# CAM-M8Q-Breakout_v10.net
KiCad netlist of a schematic drawn in EAGLE
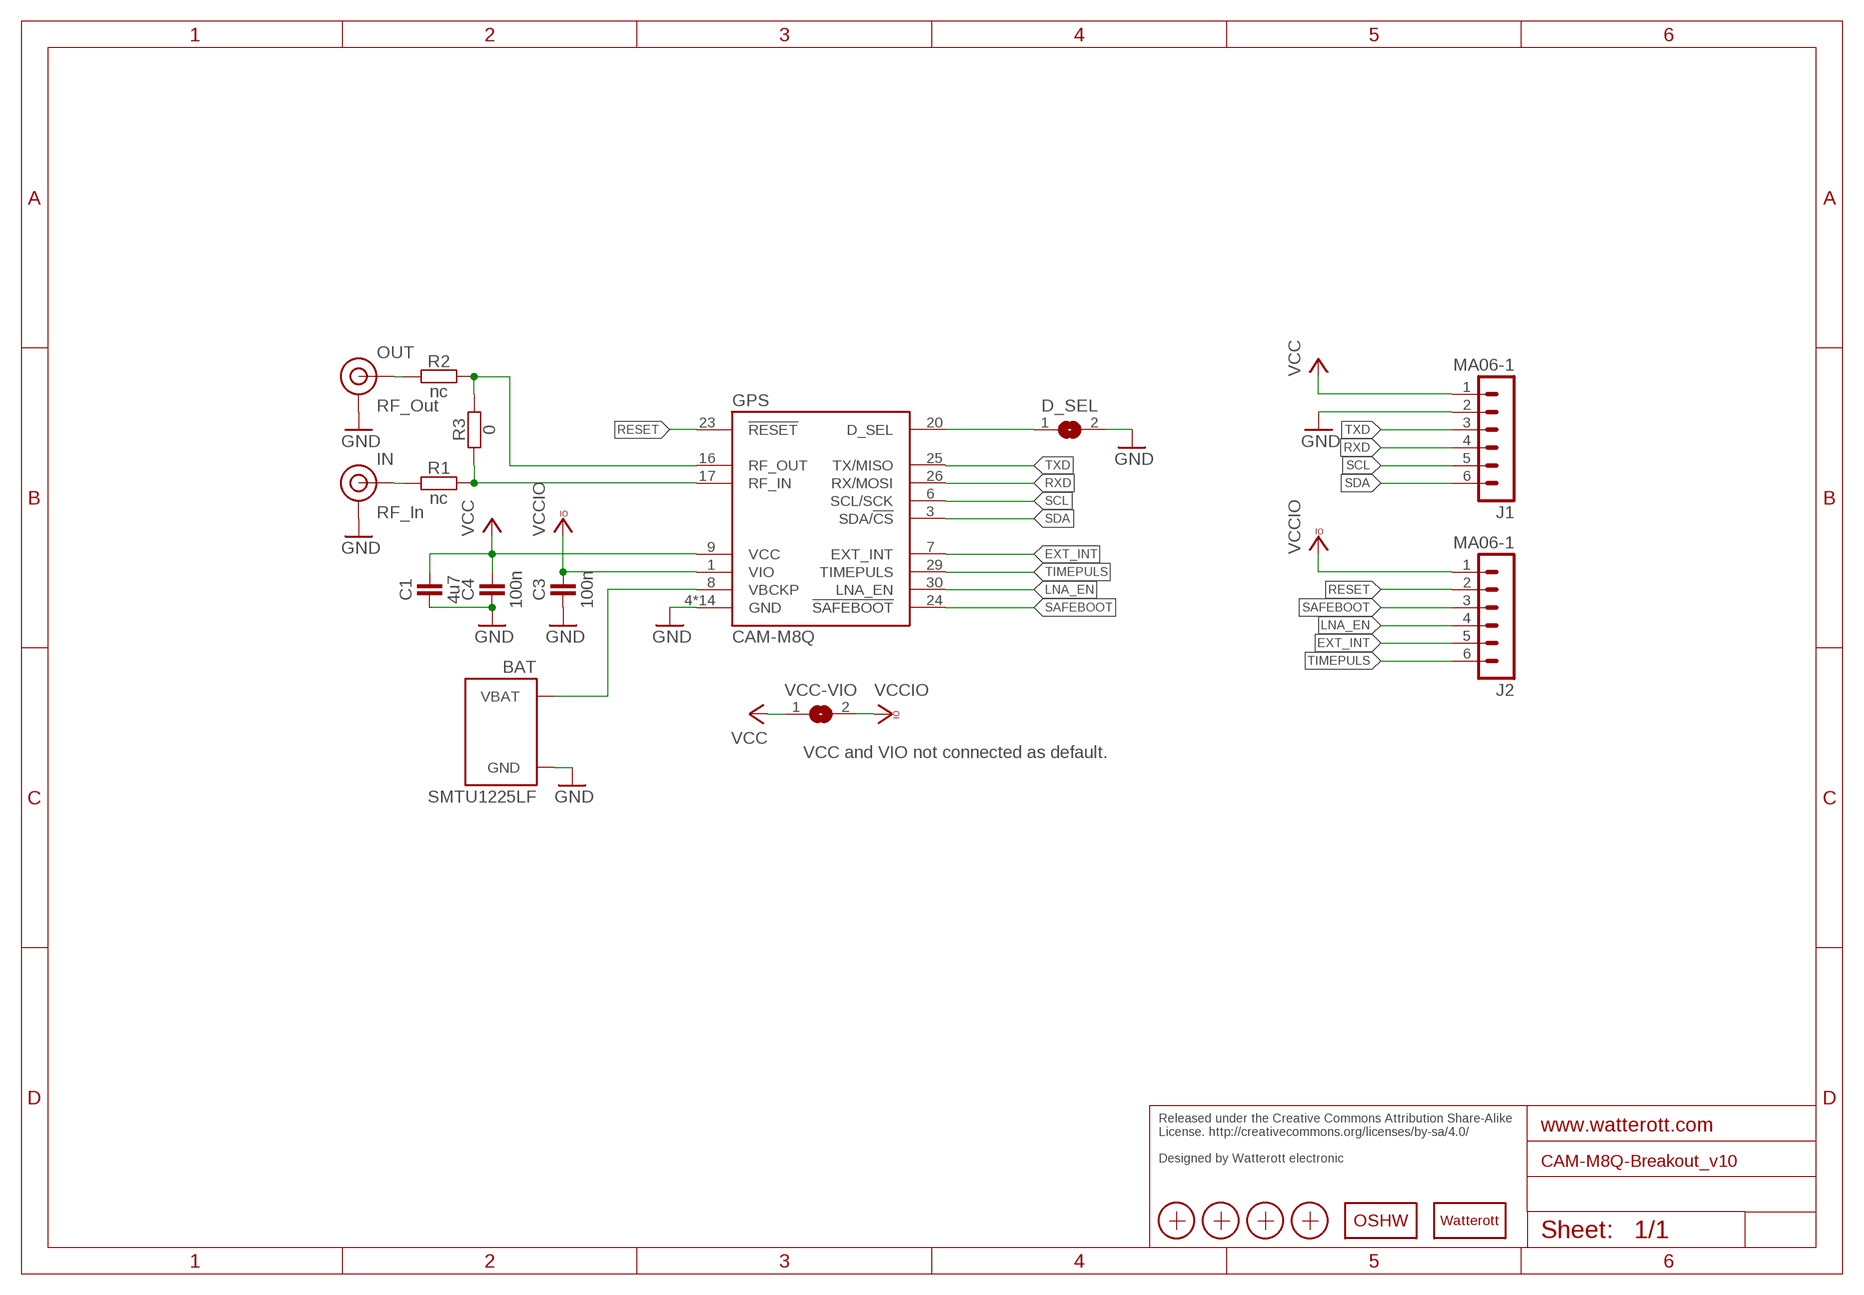
[diagram p0: schematic, sheet 1]

(export (version "E")
  (design (tool "Eeschema 10.0.6"))
  (components
    (comp (ref "BAT")
      (value "SMTU1225LF")
      (footprint "eagle-import:BAT-SMTU1225LF")
      (libsource (lib "eagle-import") (part "BATTERY-SMTU1225LF"))
    )
    (comp (ref "C1")
      (value "4u7")
      (footprint "eagle-import:C0402")
      (libsource (lib "eagle-import") (part "CAPACITOR-0402"))
    )
    (comp (ref "C3")
      (value "100n")
      (footprint "eagle-import:C0402")
      (libsource (lib "eagle-import") (part "CAPACITOR-0402"))
    )
    (comp (ref "C4")
      (value "100n")
      (footprint "eagle-import:C0402")
      (libsource (lib "eagle-import") (part "CAPACITOR-0402"))
    )
    (comp (ref "D_SEL")
      (value "JUMPER2-0603-NC")
      (footprint "eagle-import:JUMPER2-0603_NC")
      (libsource (lib "eagle-import") (part "JUMPER2-0603-NC"))
    )
    (comp (ref "GPS")
      (value "CAM-M8Q")
      (footprint "eagle-import:CAM-M8Q")
      (libsource (lib "eagle-import") (part "CAM-M8Q"))
    )
    (comp (ref "IN")
      (value "RF_In")
      (footprint "eagle-import:U.FL")
      (libsource (lib "eagle-import") (part "U.FL"))
    )
    (comp (ref "J1")
      (value "MA06-1")
      (footprint "eagle-import:MA06-1")
      (libsource (lib "eagle-import") (part "MA06-1"))
    )
    (comp (ref "J2")
      (value "MA06-1")
      (footprint "eagle-import:MA06-1")
      (libsource (lib "eagle-import") (part "MA06-1"))
    )
    (comp (ref "LOGO1")
      (value "LOGO-S_PLACE_M")
      (footprint "eagle-import:SPARK_TPLACE_M")
      (libsource (lib "eagle-import") (part "LOGO-S_PLACE_M"))
    )
    (comp (ref "LOGO2")
      (value "OSHW_LOGOX0070")
      (footprint "eagle-import:OSHW_6X70")
      (libsource (lib "eagle-import") (part "OSHW_LOGOX0070"))
    )
    (comp (ref "OUT")
      (value "RF_Out")
      (footprint "eagle-import:U.FL")
      (libsource (lib "eagle-import") (part "U.FL"))
    )
    (comp (ref "R1")
      (value "nc")
      (footprint "eagle-import:C0402")
      (libsource (lib "eagle-import") (part "RESISTOR-0402"))
    )
    (comp (ref "R2")
      (value "nc")
      (footprint "eagle-import:C0402")
      (libsource (lib "eagle-import") (part "RESISTOR-0402"))
    )
    (comp (ref "R3")
      (value "0")
      (footprint "eagle-import:C0402")
      (libsource (lib "eagle-import") (part "RESISTOR-0402"))
    )
    (comp (ref "VCC-VIO")
      (value "JUMPER2-0603-NC")
      (footprint "eagle-import:JUMPER2-0603_NC")
      (libsource (lib "eagle-import") (part "JUMPER2-0603-NC"))
    )
    (comp (ref "X1")
      (value "PASSER-07")
      (footprint "eagle-import:PASSER_07MM")
      (libsource (lib "eagle-import") (part "PASSER-07"))
    )
    (comp (ref "X2")
      (value "PASSER-07")
      (footprint "eagle-import:PASSER_07MM")
      (libsource (lib "eagle-import") (part "PASSER-07"))
    )
    (comp (ref "X3")
      (value "PASSER-07")
      (footprint "eagle-import:PASSER_07MM")
      (libsource (lib "eagle-import") (part "PASSER-07"))
    )
    (comp (ref "X4")
      (value "PASSER-07")
      (footprint "eagle-import:PASSER_07MM")
      (libsource (lib "eagle-import") (part "PASSER-07"))
    )
  )
  (nets
    (net (code "1") (name "EXT_INT") (class "Default")
      (node (ref "GPS") (pin "7") (pinfunction "EXT_INT_7") (pintype "bidirectional"))
      (node (ref "J2") (pin "5") (pinfunction "5_5") (pintype "passive"))
    )
    (net (code "2") (name "GND") (class "Default")
      (node (ref "BAT") (pin "-") (pinfunction "GND_-") (pintype "power_in"))
      (node (ref "C1") (pin "1") (pinfunction "1_1") (pintype "passive"))
      (node (ref "C3") (pin "1") (pinfunction "1_1") (pintype "passive"))
      (node (ref "C4") (pin "1") (pinfunction "1_1") (pintype "passive"))
      (node (ref "D_SEL") (pin "2") (pinfunction "2_2") (pintype "passive"))
      (node (ref "GPS") (pin "10") (pinfunction "GND_10") (pintype "power_in"))
      (node (ref "GPS") (pin "11") (pinfunction "GND_11") (pintype "power_in"))
      (node (ref "GPS") (pin "12") (pinfunction "GND_12") (pintype "power_in"))
      (node (ref "GPS") (pin "13") (pinfunction "GND_13") (pintype "power_in"))
      (node (ref "GPS") (pin "14") (pinfunction "GND_14") (pintype "power_in"))
      (node (ref "GPS") (pin "15") (pinfunction "GND_15") (pintype "power_in"))
      (node (ref "GPS") (pin "18") (pinfunction "GND_18") (pintype "power_in"))
      (node (ref "GPS") (pin "19") (pinfunction "GND_19") (pintype "power_in"))
      (node (ref "GPS") (pin "21") (pinfunction "GND_21") (pintype "power_in"))
      (node (ref "GPS") (pin "22") (pinfunction "GND_22") (pintype "power_in"))
      (node (ref "GPS") (pin "27") (pinfunction "GND_27") (pintype "power_in"))
      (node (ref "GPS") (pin "31") (pinfunction "GND_31") (pintype "power_in"))
      (node (ref "GPS") (pin "4") (pinfunction "GND_4") (pintype "power_in"))
      (node (ref "GPS") (pin "5") (pinfunction "GND_5") (pintype "power_in"))
      (node (ref "IN") (pin "1") (pinfunction "GND_1") (pintype "bidirectional"))
      (node (ref "IN") (pin "2") (pinfunction "GND_2") (pintype "bidirectional"))
      (node (ref "J1") (pin "2") (pinfunction "2_2") (pintype "passive"))
      (node (ref "OUT") (pin "1") (pinfunction "GND_1") (pintype "bidirectional"))
      (node (ref "OUT") (pin "2") (pinfunction "GND_2") (pintype "bidirectional"))
    )
    (net (code "3") (name "LNA_EN") (class "Default")
      (node (ref "GPS") (pin "30") (pinfunction "LNA_EN_30") (pintype "bidirectional"))
      (node (ref "J2") (pin "4") (pinfunction "4_4") (pintype "passive"))
    )
    (net (code "4") (name "Net-(BAT-VBAT)") (class "Default")
      (node (ref "BAT") (pin "+") (pinfunction "VBAT_+") (pintype "power_in"))
      (node (ref "GPS") (pin "8") (pinfunction "VBCKP_8") (pintype "power_in"))
    )
    (net (code "5") (name "Net-(GPS-D_SEL)") (class "Default")
      (node (ref "D_SEL") (pin "1") (pinfunction "1_1") (pintype "passive"))
      (node (ref "GPS") (pin "20") (pinfunction "D_SEL_20") (pintype "bidirectional"))
    )
    (net (code "6") (name "Net-(GPS-RF_IN)") (class "Default")
      (node (ref "GPS") (pin "17") (pinfunction "RF_IN_17") (pintype "input"))
      (node (ref "R1") (pin "2") (pinfunction "2_2") (pintype "passive"))
      (node (ref "R3") (pin "1") (pinfunction "1_1") (pintype "passive"))
    )
    (net (code "7") (name "Net-(GPS-RF_OUT)") (class "Default")
      (node (ref "GPS") (pin "16") (pinfunction "RF_OUT_16") (pintype "output"))
      (node (ref "R2") (pin "2") (pinfunction "2_2") (pintype "passive"))
      (node (ref "R3") (pin "2") (pinfunction "2_2") (pintype "passive"))
    )
    (net (code "8") (name "Net-(IN-SIGNAL)") (class "Default")
      (node (ref "IN") (pin "FEED") (pinfunction "SIGNAL_FEED") (pintype "bidirectional"))
      (node (ref "R1") (pin "1") (pinfunction "1_1") (pintype "passive"))
    )
    (net (code "9") (name "Net-(OUT-SIGNAL)") (class "Default")
      (node (ref "OUT") (pin "FEED") (pinfunction "SIGNAL_FEED") (pintype "bidirectional"))
      (node (ref "R2") (pin "1") (pinfunction "1_1") (pintype "passive"))
    )
    (net (code "10") (name "RESET") (class "Default")
      (node (ref "GPS") (pin "23") (pinfunction "~{RESET}_23") (pintype "input"))
      (node (ref "J2") (pin "2") (pinfunction "2_2") (pintype "passive"))
    )
    (net (code "11") (name "RXD") (class "Default")
      (node (ref "GPS") (pin "26") (pinfunction "RX/MOSI_26") (pintype "input"))
      (node (ref "J1") (pin "4") (pinfunction "4_4") (pintype "passive"))
    )
    (net (code "12") (name "SAFEBOOT") (class "Default")
      (node (ref "GPS") (pin "24") (pinfunction "~{SAFEBOOT}_24") (pintype "bidirectional"))
      (node (ref "J2") (pin "3") (pinfunction "3_3") (pintype "passive"))
    )
    (net (code "13") (name "SCL") (class "Default")
      (node (ref "GPS") (pin "6") (pinfunction "SCL/SCK_6") (pintype "bidirectional"))
      (node (ref "J1") (pin "5") (pinfunction "5_5") (pintype "passive"))
    )
    (net (code "14") (name "SDA") (class "Default")
      (node (ref "GPS") (pin "3") (pinfunction "SDA/~{CS}_3") (pintype "bidirectional"))
      (node (ref "J1") (pin "6") (pinfunction "6_6") (pintype "passive"))
    )
    (net (code "15") (name "TIMEPULS") (class "Default")
      (node (ref "GPS") (pin "29") (pinfunction "TIMEPULS_29") (pintype "output"))
      (node (ref "J2") (pin "6") (pinfunction "6_6") (pintype "passive"))
    )
    (net (code "16") (name "TXD") (class "Default")
      (node (ref "GPS") (pin "25") (pinfunction "TX/MISO_25") (pintype "output"))
      (node (ref "J1") (pin "3") (pinfunction "3_3") (pintype "passive"))
    )
    (net (code "17") (name "VCC") (class "Default")
      (node (ref "C1") (pin "2") (pinfunction "2_2") (pintype "passive"))
      (node (ref "C4") (pin "2") (pinfunction "2_2") (pintype "passive"))
      (node (ref "GPS") (pin "9") (pinfunction "VCC_9") (pintype "power_in"))
      (node (ref "J1") (pin "1") (pinfunction "1_1") (pintype "passive"))
      (node (ref "VCC-VIO") (pin "1") (pinfunction "1_1") (pintype "passive"))
    )
    (net (code "18") (name "VCCIO") (class "Default")
      (node (ref "C3") (pin "2") (pinfunction "2_2") (pintype "passive"))
      (node (ref "GPS") (pin "1") (pinfunction "VIO_1") (pintype "power_in"))
      (node (ref "J2") (pin "1") (pinfunction "1_1") (pintype "passive"))
      (node (ref "VCC-VIO") (pin "2") (pinfunction "2_2") (pintype "passive"))
    )
  )
)
